# Power_Supply.net
KiCad netlist of a schematic drawn in Altium Designer
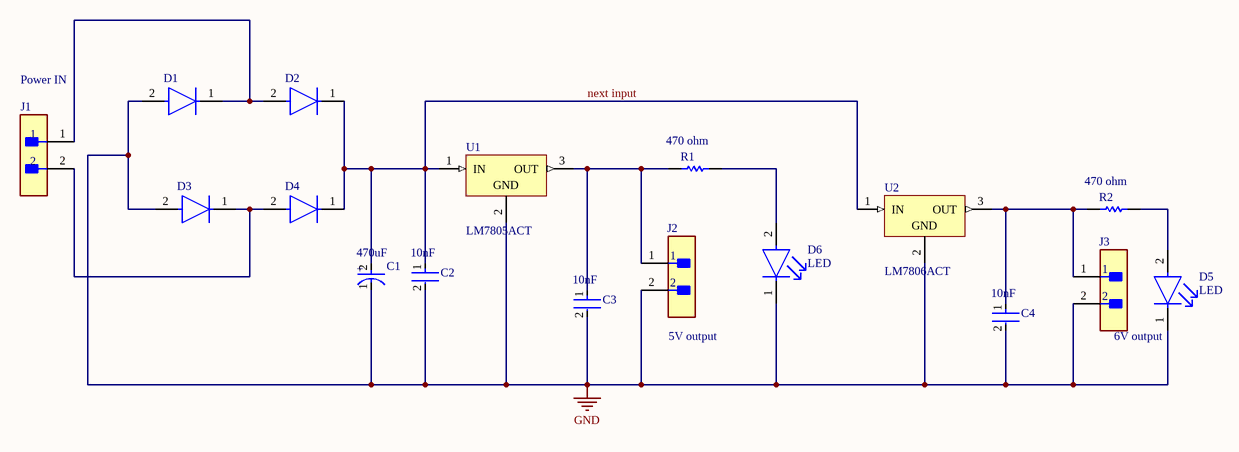
[diagram p0: Power_Supply.SchDoc]

(export (version "E")
  (design (tool "Eeschema 10.0.6"))
  (components
    (comp (ref "C1")
      (value "EEUTA1H331S")
      (footprint "FP-RAD-TH-D_16_0_5-L_15_1-MFG")
      (description "Aluminum Electrolytic Capacitors (Radial Lead Type) AEC-Q200 Qualified 330uF ±20% 50V")
      (fields (field (name "TOLERANCE") "20%") (field (name "CAPACITANCE") "470uF"))
      (libsource (lib "Altium Content Vault") (part "a00bbbee19879c290e62620ae7e47b1"))
    )
    (comp (ref "C2")
      (value "RCER71H103K0K1H03B")
      (footprint "FP-RCE0K1-MFG")
      (description "Cap Ceramic 10nF 50V X7R ±10% Radial 5mm +125°C Automotive Bulk")
      (fields (field (name "CAPACITANCE") "10nF") (field (name "TOLERANCE") "10%"))
      (libsource (lib "Altium Content Vault") (part "b4654b650e69147ec39a6b967a45e02"))
    )
    (comp (ref "C3")
      (value "RCER71H103K0K1H03B")
      (footprint "FP-RCE0K1-MFG")
      (description "Cap Ceramic 10nF 50V X7R ±10% Radial 5mm +125°C Automotive Bulk")
      (fields (field (name "CAPACITANCE") "10nF") (field (name "TOLERANCE") "10%"))
      (libsource (lib "Altium Content Vault") (part "b4654b650e69147ec39a6b967a45e02"))
    )
    (comp (ref "C4")
      (value "RCER71H103K0K1H03B")
      (footprint "FP-RCE0K1-MFG")
      (description "Cap Ceramic 10nF 50V X7R ±10% Radial 5mm +125°C Automotive Bulk")
      (fields (field (name "CAPACITANCE") "10nF") (field (name "TOLERANCE") "10%"))
      (libsource (lib "Altium Content Vault") (part "b4654b650e69147ec39a6b967a45e02"))
    )
    (comp (ref "D1")
      (value "1N4007")
      (footprint "FP-1N4007-MFG")
      (description "Rectifier diode 1000 V 1 A DO-41, ,")
      (fields
        (field (name "MANUFACTURER") "Diotec")
        (field (name "OCTOPART") "https://octopart.com/1n4007-diotec-4040411")
      )
      (libsource (lib "Altium Content Vault") (part "d7152d700b627762746794eb795d46e"))
    )
    (comp (ref "D2")
      (value "1N4007")
      (footprint "FP-1N4007-MFG")
      (description "Rectifier diode 1000 V 1 A DO-41, ,")
      (fields
        (field (name "MANUFACTURER") "Diotec")
        (field (name "OCTOPART") "https://octopart.com/1n4007-diotec-4040411")
      )
      (libsource (lib "Altium Content Vault") (part "d7152d700b627762746794eb795d46e"))
    )
    (comp (ref "D3")
      (value "1N4007")
      (footprint "FP-1N4007-MFG")
      (description "Rectifier diode 1000 V 1 A DO-41, ,")
      (fields
        (field (name "MANUFACTURER") "Diotec")
        (field (name "OCTOPART") "https://octopart.com/1n4007-diotec-4040411")
      )
      (libsource (lib "Altium Content Vault") (part "d7152d700b627762746794eb795d46e"))
    )
    (comp (ref "D4")
      (value "1N4007")
      (footprint "FP-1N4007-MFG")
      (description "Rectifier diode 1000 V 1 A DO-41, ,")
      (fields
        (field (name "MANUFACTURER") "Diotec")
        (field (name "OCTOPART") "https://octopart.com/1n4007-diotec-4040411")
      )
      (libsource (lib "Altium Content Vault") (part "d7152d700b627762746794eb795d46e"))
    )
    (comp (ref "D5")
      (value "LED")
      (footprint "FP-HLMP-4700-MFG")
      (description "LED RED DIFFUSED T-1 3/4 T/H")
      (fields
        (field (name "OCTOPART") "https://octopart.com/hlmp-4700-broadcom-71130526")
        (field (name "MANUFACTURER") "Broadcom")
      )
      (libsource (lib "Altium Content Vault") (part "8706943c75ba83719d021d2fdc84c58"))
    )
    (comp (ref "D6")
      (value "LED")
      (footprint "FP-HLMP-4700-MFG")
      (description "LED RED DIFFUSED T-1 3/4 T/H")
      (fields
        (field (name "OCTOPART") "https://octopart.com/hlmp-4700-broadcom-71130526")
        (field (name "MANUFACTURER") "Broadcom")
      )
      (libsource (lib "Altium Content Vault") (part "8706943c75ba83719d021d2fdc84c58"))
    )
    (comp (ref "J1")
      (value "TSW-102-07-L-S")
      (footprint "FP-TSW-102-07-L-S-MFG")
      (description "CONN HEADER VERT 2POS 2.54MM")
      (libsource (lib "") (part "3bc925449376181038e59eaffc5286c_1"))
    )
    (comp (ref "J2")
      (value "TSW-102-07-L-S")
      (footprint "FP-TSW-102-07-L-S-MFG")
      (description "CONN HEADER VERT 2POS 2.54MM")
      (libsource (lib "Altium Content Vault") (part "3bc925449376181038e59eaffc5286c"))
    )
    (comp (ref "J3")
      (value "TSW-102-07-L-S")
      (footprint "FP-TSW-102-07-L-S-MFG")
      (description "CONN HEADER VERT 2POS 2.54MM")
      (libsource (lib "Altium Content Vault") (part "3bc925449376181038e59eaffc5286c"))
    )
    (comp (ref "R1")
      (value "MFR-25FBF52-1K")
      (footprint "RESA60-630X240")
      (description "Axial Resistor, 1 KOhm, +/- 1%, 250 mW, -55 to 155 degC, 2-Pin THD, RoHS, Bulk")
      (fields (field (name "TOLERANCE") "1%") (field (name "RESISTANCE") "470 ohm"))
      (libsource (lib "Altium Content Vault") (part "RES-2"))
    )
    (comp (ref "R2")
      (value "MFR-25FBF52-1K")
      (footprint "RESA60-630X240")
      (description "Axial Resistor, 1 KOhm, +/- 1%, 250 mW, -55 to 155 degC, 2-Pin THD, RoHS, Bulk")
      (fields (field (name "TOLERANCE") "1%") (field (name "RESISTANCE") "470 ohm"))
      (libsource (lib "Altium Content Vault") (part "RES-2"))
    )
    (comp (ref "U1")
      (value "LM7805ACT")
      (footprint "FAIR-TO-220-3")
      (description "Positive Voltage Regulator, 5 V, 1 A, 0 to 125 degC, 3-Pin TO-220, RoHS, Tube")
      (fields (field (name "MANUFACTURER") "Fairchild"))
      (libsource (lib "Altium Content Vault") (part "FAIR-LM7805CT-TO220-3"))
    )
    (comp (ref "U2")
      (value "LM7806ACT")
      (footprint "FAIR-TO-220-3")
      (description "Positive Voltage Regulator, 5 V, 1 A, 0 to 125 degC, 3-Pin TO-220, RoHS, Tube")
      (fields (field (name "MANUFACTURER") "Fairchild"))
      (libsource (lib "Altium Content Vault") (part "FAIR-LM7805CT-TO220-3"))
    )
  )
  (nets
    (net (code "1") (name "/next input") (class "Default")
      (node (ref "C1") (pin "2") (pinfunction "A_2") (pintype "passive"))
      (node (ref "C2") (pin "1") (pinfunction "1_1") (pintype "passive"))
      (node (ref "D2") (pin "1") (pinfunction "C_1") (pintype "passive"))
      (node (ref "D4") (pin "1") (pinfunction "C_1") (pintype "passive"))
      (node (ref "U1") (pin "1") (pinfunction "IN_1") (pintype "input"))
      (node (ref "U2") (pin "1") (pinfunction "IN_1") (pintype "input"))
    )
    (net (code "2") (name "GND") (class "Default")
      (node (ref "C1") (pin "1") (pinfunction "C_1") (pintype "passive"))
      (node (ref "C2") (pin "2") (pinfunction "2_2") (pintype "passive"))
      (node (ref "C3") (pin "2") (pinfunction "2_2") (pintype "passive"))
      (node (ref "C4") (pin "2") (pinfunction "2_2") (pintype "passive"))
      (node (ref "D1") (pin "2") (pinfunction "A_2") (pintype "passive"))
      (node (ref "D3") (pin "2") (pinfunction "A_2") (pintype "passive"))
      (node (ref "D5") (pin "1") (pinfunction "C_1") (pintype "passive"))
      (node (ref "D6") (pin "1") (pinfunction "C_1") (pintype "passive"))
      (node (ref "J2") (pin "2") (pinfunction "2_2") (pintype "passive"))
      (node (ref "J3") (pin "2") (pinfunction "2_2") (pintype "passive"))
      (node (ref "U1") (pin "2") (pinfunction "GND_2") (pintype "power_in"))
      (node (ref "U2") (pin "2") (pinfunction "GND_2") (pintype "power_in"))
    )
    (net (code "3") (name "Net-(D1-C)") (class "Default")
      (node (ref "D1") (pin "1") (pinfunction "C_1") (pintype "passive"))
      (node (ref "D2") (pin "2") (pinfunction "A_2") (pintype "passive"))
      (node (ref "J1") (pin "1") (pinfunction "1_1") (pintype "passive"))
    )
    (net (code "4") (name "Net-(D3-C)") (class "Default")
      (node (ref "D3") (pin "1") (pinfunction "C_1") (pintype "passive"))
      (node (ref "D4") (pin "2") (pinfunction "A_2") (pintype "passive"))
      (node (ref "J1") (pin "2") (pinfunction "2_2") (pintype "passive"))
    )
    (net (code "5") (name "Net-(D5-A)") (class "Default")
      (node (ref "D5") (pin "2") (pinfunction "A_2") (pintype "passive"))
      (node (ref "R2") (pin "2") (pinfunction "2_2") (pintype "passive"))
    )
    (net (code "6") (name "Net-(D6-A)") (class "Default")
      (node (ref "D6") (pin "2") (pinfunction "A_2") (pintype "passive"))
      (node (ref "R1") (pin "2") (pinfunction "2_2") (pintype "passive"))
    )
    (net (code "7") (name "Net-(U1-OUT)") (class "Default")
      (node (ref "C3") (pin "1") (pinfunction "1_1") (pintype "passive"))
      (node (ref "J2") (pin "1") (pinfunction "1_1") (pintype "passive"))
      (node (ref "R1") (pin "1") (pinfunction "1_1") (pintype "passive"))
      (node (ref "U1") (pin "3") (pinfunction "OUT_3") (pintype "output"))
    )
    (net (code "8") (name "Net-(U2-OUT)") (class "Default")
      (node (ref "C4") (pin "1") (pinfunction "1_1") (pintype "passive"))
      (node (ref "J3") (pin "1") (pinfunction "1_1") (pintype "passive"))
      (node (ref "R2") (pin "1") (pinfunction "1_1") (pintype "passive"))
      (node (ref "U2") (pin "3") (pinfunction "OUT_3") (pintype "output"))
    )
  )
)
